# design.net
KiCad netlist of a schematic drawn in Altium Designer
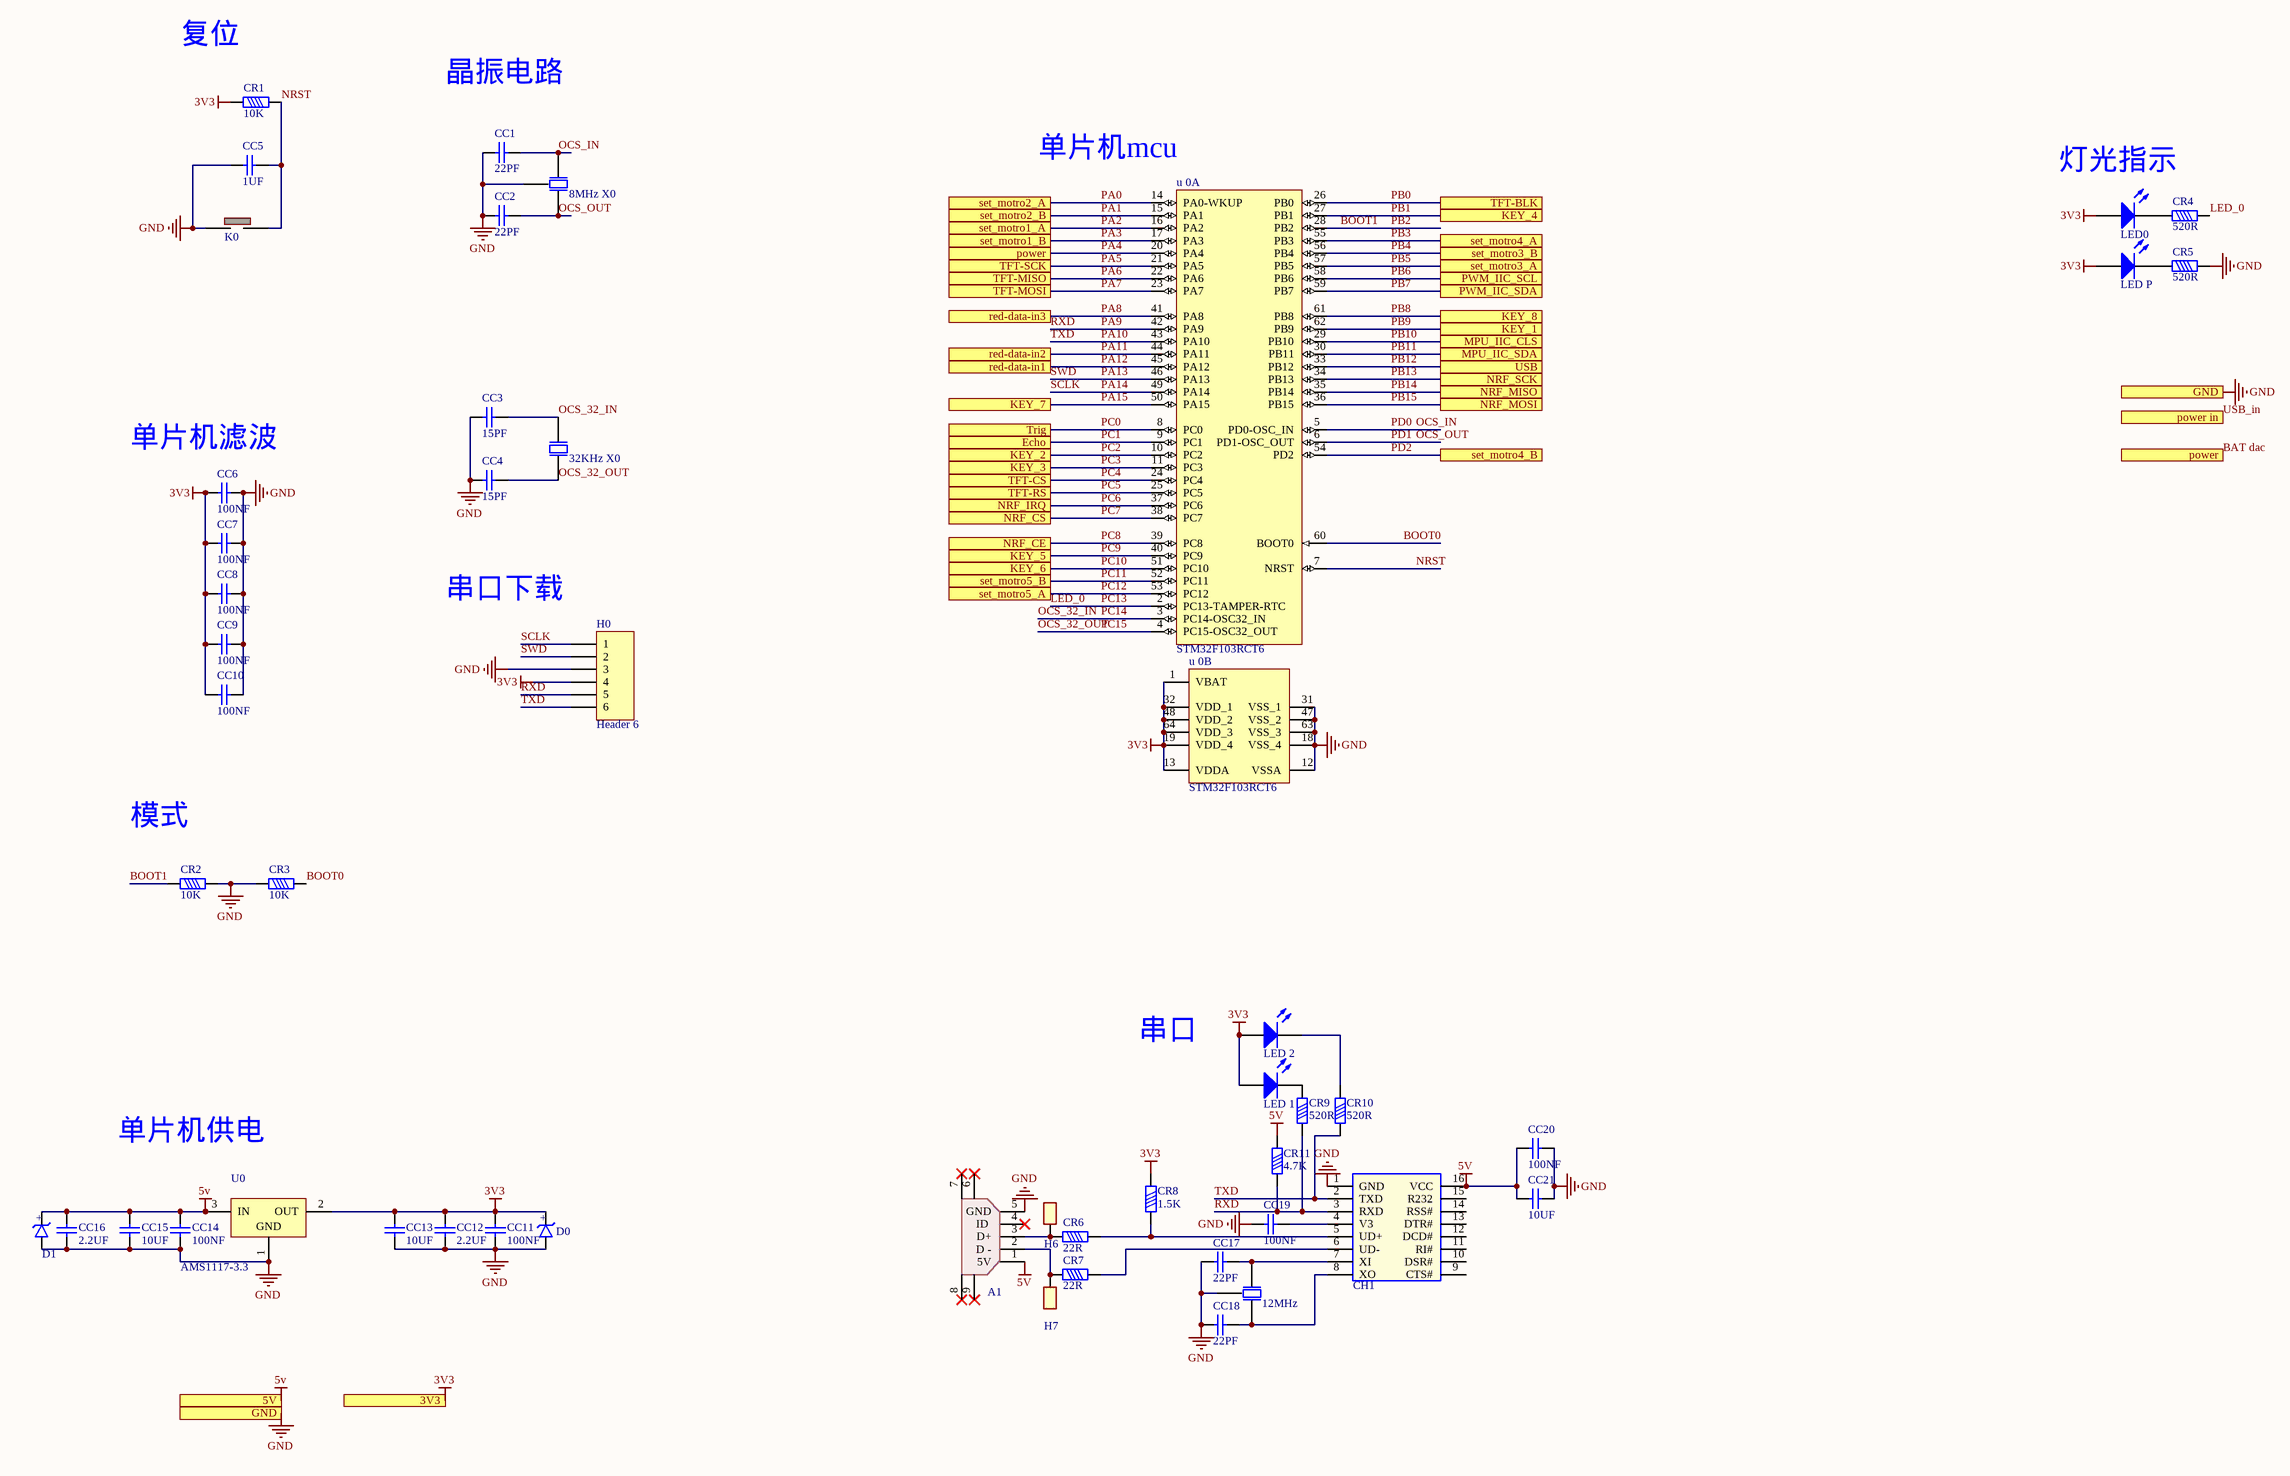
[diagram p0: 瓦力驱动主控原理图.SchDoc]

(export (version "E")
  (design (tool "Eeschema 10.0.6"))
  (components
    (comp (ref "8MHz X0")
      (value "XTAL 3225 8M")
      (footprint "T 3225")
      (libsource (lib "tianxiaohua_Schlib") (part "XTAL 3225 8M"))
    )
    (comp (ref "12MHz")
      (value "XTAL 3225 8M")
      (footprint "T 3225")
      (libsource (lib "tianxiaohua_Schlib") (part "XTAL 3225 8M"))
    )
    (comp (ref "32KHz X0")
      (value "XTAL 3215 32.768kKHz")
      (footprint "T 3215")
      (libsource (lib "tianxiaohua_Schlib") (part "XTAL 3215 32.768kKHz"))
    )
    (comp (ref "A1")
      (value "Micro USB")
      (footprint "Micro USB")
      (libsource (lib "tianxiaohua_Schlib") (part "Micro USB"))
    )
    (comp (ref "CC1")
      (value "22PF")
      (footprint "CC1608-0603")
      (description "Polarized Capacitor (Radial)")
      (fields (field (name "Comment") "Cap Chip 0603") (field (name "PUBLISHER") "Altium Limited"))
      (libsource (lib "EButterflyIntegratedLibrary") (part "Cap Chip 0603"))
    )
    (comp (ref "CC2")
      (value "22PF")
      (footprint "CC1608-0603")
      (description "Polarized Capacitor (Radial)")
      (fields (field (name "Comment") "Cap Chip 0603") (field (name "PUBLISHER") "Altium Limited"))
      (libsource (lib "EButterflyIntegratedLibrary") (part "Cap Chip 0603"))
    )
    (comp (ref "CC3")
      (value "15PF")
      (footprint "CC1608-0603")
      (description "Polarized Capacitor (Radial)")
      (fields (field (name "Comment") "Cap Chip 0603") (field (name "PUBLISHER") "Altium Limited"))
      (libsource (lib "EButterflyIntegratedLibrary") (part "Cap Chip 0603"))
    )
    (comp (ref "CC4")
      (value "15PF")
      (footprint "CC1608-0603")
      (description "Polarized Capacitor (Radial)")
      (fields (field (name "Comment") "Cap Chip 0603") (field (name "PUBLISHER") "Altium Limited"))
      (libsource (lib "EButterflyIntegratedLibrary") (part "Cap Chip 0603"))
    )
    (comp (ref "CC5")
      (value "1UF")
      (footprint "CC1608-0603")
      (description "Polarized Capacitor (Radial)")
      (fields (field (name "Comment") "Cap Chip 0603") (field (name "PUBLISHER") "Altium Limited"))
      (libsource (lib "EButterflyIntegratedLibrary") (part "Cap Chip 0603"))
    )
    (comp (ref "CC6")
      (value "100NF")
      (footprint "CC1608-0603")
      (description "Polarized Capacitor (Radial)")
      (fields (field (name "Comment") "Cap Chip 0603") (field (name "PUBLISHER") "Altium Limited"))
      (libsource (lib "EButterflyIntegratedLibrary") (part "Cap Chip 0603"))
    )
    (comp (ref "CC7")
      (value "100NF")
      (footprint "CC1608-0603")
      (description "Polarized Capacitor (Radial)")
      (fields (field (name "Comment") "Cap Chip 0603") (field (name "PUBLISHER") "Altium Limited"))
      (libsource (lib "EButterflyIntegratedLibrary") (part "Cap Chip 0603"))
    )
    (comp (ref "CC8")
      (value "100NF")
      (footprint "CC1608-0603")
      (description "Polarized Capacitor (Radial)")
      (fields (field (name "Comment") "Cap Chip 0603") (field (name "PUBLISHER") "Altium Limited"))
      (libsource (lib "EButterflyIntegratedLibrary") (part "Cap Chip 0603"))
    )
    (comp (ref "CC9")
      (value "100NF")
      (footprint "CC1608-0603")
      (description "Polarized Capacitor (Radial)")
      (fields (field (name "Comment") "Cap Chip 0603") (field (name "PUBLISHER") "Altium Limited"))
      (libsource (lib "EButterflyIntegratedLibrary") (part "Cap Chip 0603"))
    )
    (comp (ref "CC10")
      (value "100NF")
      (footprint "CC1608-0603")
      (description "Polarized Capacitor (Radial)")
      (fields (field (name "Comment") "Cap Chip 0603") (field (name "PUBLISHER") "Altium Limited"))
      (libsource (lib "EButterflyIntegratedLibrary") (part "Cap Chip 0603"))
    )
    (comp (ref "CC11")
      (value "100NF")
      (footprint "CC1608-0603")
      (description "Polarized Capacitor (Radial)")
      (fields (field (name "Comment") "Cap Chip 0603") (field (name "PUBLISHER") "Altium Limited"))
      (libsource (lib "EButterflyIntegratedLibrary") (part "Cap Chip 0603"))
    )
    (comp (ref "CC12")
      (value "2.2UF")
      (footprint "CC1608-0603")
      (description "Polarized Capacitor (Radial)")
      (fields (field (name "Comment") "Cap Chip 0603") (field (name "PUBLISHER") "Altium Limited"))
      (libsource (lib "EButterflyIntegratedLibrary") (part "Cap Chip 0603"))
    )
    (comp (ref "CC13")
      (value "10UF")
      (footprint "CC1608-0603")
      (description "Polarized Capacitor (Radial)")
      (fields (field (name "Comment") "Cap Chip 0603") (field (name "PUBLISHER") "Altium Limited"))
      (libsource (lib "EButterflyIntegratedLibrary") (part "Cap Chip 0603"))
    )
    (comp (ref "CC14")
      (value "100NF")
      (footprint "CC1608-0603")
      (description "Polarized Capacitor (Radial)")
      (fields (field (name "Comment") "Cap Chip 0603") (field (name "PUBLISHER") "Altium Limited"))
      (libsource (lib "EButterflyIntegratedLibrary") (part "Cap Chip 0603"))
    )
    (comp (ref "CC15")
      (value "10UF")
      (footprint "CC1608-0603")
      (description "Polarized Capacitor (Radial)")
      (fields (field (name "Comment") "Cap Chip 0603") (field (name "PUBLISHER") "Altium Limited"))
      (libsource (lib "EButterflyIntegratedLibrary") (part "Cap Chip 0603"))
    )
    (comp (ref "CC16")
      (value "2.2UF")
      (footprint "CC1608-0603")
      (description "Polarized Capacitor (Radial)")
      (fields (field (name "Comment") "Cap Chip 0603") (field (name "PUBLISHER") "Altium Limited"))
      (libsource (lib "EButterflyIntegratedLibrary") (part "Cap Chip 0603"))
    )
    (comp (ref "CC17")
      (value "22PF")
      (footprint "CC1608-0603")
      (description "Polarized Capacitor (Radial)")
      (fields (field (name "Comment") "Cap Chip 0603") (field (name "PUBLISHER") "Altium Limited"))
      (libsource (lib "EButterflyIntegratedLibrary") (part "Cap Chip 0603"))
    )
    (comp (ref "CC18")
      (value "22PF")
      (footprint "CC1608-0603")
      (description "Polarized Capacitor (Radial)")
      (fields (field (name "Comment") "Cap Chip 0603") (field (name "PUBLISHER") "Altium Limited"))
      (libsource (lib "EButterflyIntegratedLibrary") (part "Cap Chip 0603"))
    )
    (comp (ref "CC19")
      (value "100NF")
      (footprint "CC1608-0603")
      (description "Polarized Capacitor (Radial)")
      (fields (field (name "Comment") "Cap Chip 0603") (field (name "PUBLISHER") "Altium Limited"))
      (libsource (lib "EButterflyIntegratedLibrary") (part "Cap Chip 0603"))
    )
    (comp (ref "CC20")
      (value "100NF")
      (footprint "CC1608-0603")
      (description "Polarized Capacitor (Radial)")
      (fields (field (name "Comment") "Cap Chip 0603") (field (name "PUBLISHER") "Altium Limited"))
      (libsource (lib "EButterflyIntegratedLibrary") (part "Cap Chip 0603"))
    )
    (comp (ref "CC21")
      (value "10UF")
      (footprint "CC1608-0603")
      (description "Polarized Capacitor (Radial)")
      (fields (field (name "Comment") "Cap Chip 0603") (field (name "PUBLISHER") "Altium Limited"))
      (libsource (lib "EButterflyIntegratedLibrary") (part "Cap Chip 0603"))
    )
    (comp (ref "CH1")
      (value "CH340G")
      (footprint "SOP16")
      (description "串口转USB")
      (libsource (lib "tianxiaohua_Schlib") (part "CH340G"))
    )
    (comp (ref "CR1")
      (value "10K")
      (footprint "CR1608-0603")
      (description "Resistor")
      (fields (field (name "Comment") "Resistor Chip 0603") (field (name "PUBLISHER") "Altium Limited"))
      (libsource (lib "EButterflyIntegratedLibrary") (part "Resistor Chip 0603"))
    )
    (comp (ref "CR2")
      (value "10K")
      (footprint "CR1608-0603")
      (description "Resistor")
      (fields (field (name "Comment") "Resistor Chip 0603") (field (name "PUBLISHER") "Altium Limited"))
      (libsource (lib "EButterflyIntegratedLibrary") (part "Resistor Chip 0603"))
    )
    (comp (ref "CR3")
      (value "10K")
      (footprint "CR1608-0603")
      (description "Resistor")
      (fields (field (name "Comment") "Resistor Chip 0603") (field (name "PUBLISHER") "Altium Limited"))
      (libsource (lib "EButterflyIntegratedLibrary") (part "Resistor Chip 0603"))
    )
    (comp (ref "CR4")
      (value "520R")
      (footprint "CR1608-0603")
      (description "Resistor")
      (fields (field (name "Comment") "Resistor Chip 0603") (field (name "PUBLISHER") "Altium Limited"))
      (libsource (lib "EButterflyIntegratedLibrary") (part "Resistor Chip 0603"))
    )
    (comp (ref "CR5")
      (value "520R")
      (footprint "CR1608-0603")
      (description "Resistor")
      (fields (field (name "Comment") "Resistor Chip 0603") (field (name "PUBLISHER") "Altium Limited"))
      (libsource (lib "EButterflyIntegratedLibrary") (part "Resistor Chip 0603"))
    )
    (comp (ref "CR6")
      (value "22R")
      (footprint "CR1608-0603")
      (description "Resistor")
      (fields (field (name "Comment") "Resistor Chip 0603") (field (name "PUBLISHER") "Altium Limited"))
      (libsource (lib "EButterflyIntegratedLibrary") (part "Resistor Chip 0603"))
    )
    (comp (ref "CR7")
      (value "22R")
      (footprint "CR1608-0603")
      (description "Resistor")
      (fields (field (name "Comment") "Resistor Chip 0603") (field (name "PUBLISHER") "Altium Limited"))
      (libsource (lib "EButterflyIntegratedLibrary") (part "Resistor Chip 0603"))
    )
    (comp (ref "CR8")
      (value "1.5K")
      (footprint "CR1608-0603")
      (description "Resistor")
      (fields (field (name "Comment") "Resistor Chip 0603") (field (name "PUBLISHER") "Altium Limited"))
      (libsource (lib "") (part "Resistor Chip 0603_1"))
    )
    (comp (ref "CR9")
      (value "520R")
      (footprint "CR1608-0603")
      (description "Resistor")
      (fields (field (name "Comment") "Resistor Chip 0603") (field (name "PUBLISHER") "Altium Limited"))
      (libsource (lib "") (part "Resistor Chip 0603_1"))
    )
    (comp (ref "CR10")
      (value "520R")
      (footprint "CR1608-0603")
      (description "Resistor")
      (fields (field (name "Comment") "Resistor Chip 0603") (field (name "PUBLISHER") "Altium Limited"))
      (libsource (lib "") (part "Resistor Chip 0603_1"))
    )
    (comp (ref "CR11")
      (value "4.7K")
      (footprint "CR1608-0603")
      (description "Resistor")
      (fields (field (name "Comment") "Resistor Chip 0603") (field (name "PUBLISHER") "Altium Limited"))
      (libsource (lib "") (part "Resistor Chip 0603_1"))
    )
    (comp (ref "D0")
      (value "SMBJ3.3A")
      (footprint "DO214AA(SMB)")
      (description "3.3V稳压管，缓解瞬间电压冲击")
      (libsource (lib "tianxiaohua_Schlib") (part "SMBJ3.3A"))
    )
    (comp (ref "D1")
      (value "SMBJ3.3A")
      (footprint "DO214AA(SMB)")
      (description "3.3V稳压管，缓解瞬间电压冲击")
      (libsource (lib "tianxiaohua_Schlib") (part "SMBJ3.3A"))
    )
    (comp (ref "H0")
      (value "Header 6")
      (footprint "HDR1X6")
      (description "Header, 6-Pin")
      (fields (field (name "PUBLISHER") "Altium Limited"))
      (libsource (lib "EButterflyIntegratedLibrary") (part "Header 6"))
    )
    (comp (ref "H6")
      (value "H0")
      (footprint "header 1")
      (libsource (lib "tianxiaohua_Schlib") (part "header 1"))
    )
    (comp (ref "H7") (value "H0") (footprint "header 1") (libsource (lib "") (part "header 1_1")))
    (comp (ref "K0")
      (value "KEY 3*4")
      (footprint "KEY 3*4")
      (libsource (lib "tianxiaohua_Schlib") (part "KEY 3*4"))
    )
    (comp (ref "LED 1")
      (value "LED Chip")
      (footprint "CLED1608-0603")
      (description "Typical Chip LED")
      (fields (field (name "PUBLISHER") "Altium Limited"))
      (libsource (lib "EButterflyIntegratedLibrary") (part "LED Chip"))
    )
    (comp (ref "LED 2")
      (value "LED Chip")
      (footprint "CLED1608-0603")
      (description "Typical Chip LED")
      (fields (field (name "PUBLISHER") "Altium Limited"))
      (libsource (lib "EButterflyIntegratedLibrary") (part "LED Chip"))
    )
    (comp (ref "LED P")
      (value "LED Chip")
      (footprint "CLED1608-0603")
      (description "Typical Chip LED")
      (fields (field (name "PUBLISHER") "Altium Limited"))
      (libsource (lib "EButterflyIntegratedLibrary") (part "LED Chip"))
    )
    (comp (ref "LED0")
      (value "LED Chip")
      (footprint "CLED1608-0603")
      (description "Typical Chip LED")
      (fields (field (name "PUBLISHER") "Altium Limited"))
      (libsource (lib "EButterflyIntegratedLibrary") (part "LED Chip"))
    )
    (comp (ref "u 0")
      (value "STM32F103RCT6")
      (footprint "STM-LQFP64_N")
      (libsource (lib "STMicroelectronics STM32 F1") (part "STM32F103RCT6"))
    )
    (comp (ref "U0")
      (value "AMS1117-3.3")
      (footprint "SOT-223")
      (description "POSITIVE OUTPUT VOLTAGE")
      (libsource (lib "EButterflyIntegratedLibrary") (part "AMS1117"))
    )
  )
  (nets
    (net (code "1") (name "/BAT dac") (class "Default")
      (node (ref "u 0") (pin "20") (pinfunction "PA4_20") (pintype "bidirectional"))
    )
    (net (code "2") (name "/BOOT0") (class "Default")
      (node (ref "CR3") (pin "2") (pinfunction "2_2") (pintype "passive"))
      (node (ref "u 0") (pin "60") (pinfunction "BOOT0_60") (pintype "input"))
    )
    (net (code "3") (name "/BOOT1") (class "Default")
      (node (ref "CR2") (pin "1") (pinfunction "1_1") (pintype "passive"))
      (node (ref "u 0") (pin "28") (pinfunction "PB2_28") (pintype "bidirectional"))
    )
    (net (code "4") (name "/LED_0") (class "Default")
      (node (ref "CR4") (pin "2") (pinfunction "2_2") (pintype "passive"))
      (node (ref "u 0") (pin "2") (pinfunction "PC13-TAMPER-RTC_2") (pintype "bidirectional"))
    )
    (net (code "5") (name "/NRST") (class "Default")
      (node (ref "CC5") (pin "2") (pinfunction "2_2") (pintype "passive"))
      (node (ref "CR1") (pin "2") (pinfunction "2_2") (pintype "passive"))
      (node (ref "K0") (pin "2") (pinfunction "2_2") (pintype "passive"))
      (node (ref "u 0") (pin "7") (pinfunction "NRST_7") (pintype "bidirectional"))
    )
    (net (code "6") (name "/OCS_32_IN") (class "Default")
      (node (ref "32KHz X0") (pin "2") (pinfunction "OSC2_2") (pintype "passive"))
      (node (ref "CC3") (pin "2") (pinfunction "2_2") (pintype "passive"))
      (node (ref "u 0") (pin "3") (pinfunction "PC14-OSC32_IN_3") (pintype "bidirectional"))
    )
    (net (code "7") (name "/OCS_32_OUT") (class "Default")
      (node (ref "32KHz X0") (pin "1") (pinfunction "OSC1_1") (pintype "passive"))
      (node (ref "CC4") (pin "2") (pinfunction "2_2") (pintype "passive"))
      (node (ref "u 0") (pin "4") (pinfunction "PC15-OSC32_OUT_4") (pintype "bidirectional"))
    )
    (net (code "8") (name "/OCS_IN") (class "Default")
      (node (ref "8MHz X0") (pin "1") (pinfunction "OSC1_1") (pintype "passive"))
      (node (ref "CC1") (pin "2") (pinfunction "2_2") (pintype "passive"))
      (node (ref "u 0") (pin "5") (pinfunction "PD0-OSC_IN_5") (pintype "bidirectional"))
    )
    (net (code "9") (name "/OCS_OUT") (class "Default")
      (node (ref "8MHz X0") (pin "2") (pinfunction "OSC2_2") (pintype "passive"))
      (node (ref "CC2") (pin "2") (pinfunction "2_2") (pintype "passive"))
      (node (ref "u 0") (pin "6") (pinfunction "PD1-OSC_OUT_6") (pintype "bidirectional"))
    )
    (net (code "10") (name "/PA0") (class "Default")
      (node (ref "u 0") (pin "14") (pinfunction "PA0-WKUP_14") (pintype "bidirectional"))
    )
    (net (code "11") (name "/PA1") (class "Default")
      (node (ref "u 0") (pin "15") (pinfunction "PA1_15") (pintype "bidirectional"))
    )
    (net (code "12") (name "/PA2") (class "Default")
      (node (ref "u 0") (pin "16") (pinfunction "PA2_16") (pintype "bidirectional"))
    )
    (net (code "13") (name "/PA3") (class "Default")
      (node (ref "u 0") (pin "17") (pinfunction "PA3_17") (pintype "bidirectional"))
    )
    (net (code "14") (name "/PA6") (class "Default")
      (node (ref "u 0") (pin "22") (pinfunction "PA6_22") (pintype "bidirectional"))
    )
    (net (code "15") (name "/PA7") (class "Default")
      (node (ref "u 0") (pin "23") (pinfunction "PA7_23") (pintype "bidirectional"))
    )
    (net (code "16") (name "/PA8") (class "Default")
      (node (ref "u 0") (pin "41") (pinfunction "PA8_41") (pintype "bidirectional"))
    )
    (net (code "17") (name "/PA9") (class "Default")
      (node (ref "CH1") (pin "3") (pinfunction "RXD_3") (pintype "passive"))
      (node (ref "CR11") (pin "1") (pinfunction "1_1") (pintype "passive"))
      (node (ref "CR9") (pin "1") (pinfunction "1_1") (pintype "passive"))
      (node (ref "H0") (pin "5") (pinfunction "5_5") (pintype "passive"))
      (node (ref "u 0") (pin "42") (pinfunction "PA9_42") (pintype "bidirectional"))
    )
    (net (code "18") (name "/PA10") (class "Default")
      (node (ref "CH1") (pin "2") (pinfunction "TXD_2") (pintype "passive"))
      (node (ref "CR10") (pin "1") (pinfunction "1_1") (pintype "passive"))
      (node (ref "H0") (pin "6") (pinfunction "6_6") (pintype "passive"))
      (node (ref "u 0") (pin "43") (pinfunction "PA10_43") (pintype "bidirectional"))
    )
    (net (code "19") (name "/PA11") (class "Default")
      (node (ref "u 0") (pin "44") (pinfunction "PA11_44") (pintype "bidirectional"))
    )
    (net (code "20") (name "/PA12") (class "Default")
      (node (ref "u 0") (pin "45") (pinfunction "PA12_45") (pintype "bidirectional"))
    )
    (net (code "21") (name "/PA13") (class "Default")
      (node (ref "H0") (pin "2") (pinfunction "2_2") (pintype "passive"))
      (node (ref "u 0") (pin "46") (pinfunction "PA13_46") (pintype "bidirectional"))
    )
    (net (code "22") (name "/PA14") (class "Default")
      (node (ref "H0") (pin "1") (pinfunction "1_1") (pintype "passive"))
      (node (ref "u 0") (pin "49") (pinfunction "PA14_49") (pintype "bidirectional"))
    )
    (net (code "23") (name "/PA15") (class "Default")
      (node (ref "u 0") (pin "50") (pinfunction "PA15_50") (pintype "bidirectional"))
    )
    (net (code "24") (name "/PA~{5}") (class "Default")
      (node (ref "u 0") (pin "21") (pinfunction "PA5_21") (pintype "bidirectional"))
    )
    (net (code "25") (name "/PB0") (class "Default")
      (node (ref "u 0") (pin "26") (pinfunction "PB0_26") (pintype "bidirectional"))
    )
    (net (code "26") (name "/PB1") (class "Default")
      (node (ref "u 0") (pin "27") (pinfunction "PB1_27") (pintype "bidirectional"))
    )
    (net (code "27") (name "/PB3") (class "Default")
      (node (ref "u 0") (pin "55") (pinfunction "PB3_55") (pintype "bidirectional"))
    )
    (net (code "28") (name "/PB4") (class "Default")
      (node (ref "u 0") (pin "56") (pinfunction "PB4_56") (pintype "bidirectional"))
    )
    (net (code "29") (name "/PB5") (class "Default")
      (node (ref "u 0") (pin "57") (pinfunction "PB5_57") (pintype "bidirectional"))
    )
    (net (code "30") (name "/PB6") (class "Default")
      (node (ref "u 0") (pin "58") (pinfunction "PB6_58") (pintype "bidirectional"))
    )
    (net (code "31") (name "/PB7") (class "Default")
      (node (ref "u 0") (pin "59") (pinfunction "PB7_59") (pintype "bidirectional"))
    )
    (net (code "32") (name "/PB8") (class "Default")
      (node (ref "u 0") (pin "61") (pinfunction "PB8_61") (pintype "bidirectional"))
    )
    (net (code "33") (name "/PB9") (class "Default")
      (node (ref "u 0") (pin "62") (pinfunction "PB9_62") (pintype "bidirectional"))
    )
    (net (code "34") (name "/PB10") (class "Default")
      (node (ref "u 0") (pin "29") (pinfunction "PB10_29") (pintype "bidirectional"))
    )
    (net (code "35") (name "/PB11") (class "Default")
      (node (ref "u 0") (pin "30") (pinfunction "PB11_30") (pintype "bidirectional"))
    )
    (net (code "36") (name "/PB12") (class "Default")
      (node (ref "u 0") (pin "33") (pinfunction "PB12_33") (pintype "bidirectional"))
    )
    (net (code "37") (name "/PB13") (class "Default")
      (node (ref "u 0") (pin "34") (pinfunction "PB13_34") (pintype "bidirectional"))
    )
    (net (code "38") (name "/PB14") (class "Default")
      (node (ref "u 0") (pin "35") (pinfunction "PB14_35") (pintype "bidirectional"))
    )
    (net (code "39") (name "/PB15") (class "Default")
      (node (ref "u 0") (pin "36") (pinfunction "PB15_36") (pintype "bidirectional"))
    )
    (net (code "40") (name "/PC0") (class "Default")
      (node (ref "u 0") (pin "8") (pinfunction "PC0_8") (pintype "bidirectional"))
    )
    (net (code "41") (name "/PC1") (class "Default")
      (node (ref "u 0") (pin "9") (pinfunction "PC1_9") (pintype "bidirectional"))
    )
    (net (code "42") (name "/PC2") (class "Default")
      (node (ref "u 0") (pin "10") (pinfunction "PC2_10") (pintype "bidirectional"))
    )
    (net (code "43") (name "/PC3") (class "Default")
      (node (ref "u 0") (pin "11") (pinfunction "PC3_11") (pintype "bidirectional"))
    )
    (net (code "44") (name "/PC4") (class "Default")
      (node (ref "u 0") (pin "24") (pinfunction "PC4_24") (pintype "bidirectional"))
    )
    (net (code "45") (name "/PC5") (class "Default")
      (node (ref "u 0") (pin "25") (pinfunction "PC5_25") (pintype "bidirectional"))
    )
    (net (code "46") (name "/PC6") (class "Default")
      (node (ref "u 0") (pin "37") (pinfunction "PC6_37") (pintype "bidirectional"))
    )
    (net (code "47") (name "/PC7") (class "Default")
      (node (ref "u 0") (pin "38") (pinfunction "PC7_38") (pintype "bidirectional"))
    )
    (net (code "48") (name "/PC8") (class "Default")
      (node (ref "u 0") (pin "39") (pinfunction "PC8_39") (pintype "bidirectional"))
    )
    (net (code "49") (name "/PC9") (class "Default")
      (node (ref "u 0") (pin "40") (pinfunction "PC9_40") (pintype "bidirectional"))
    )
    (net (code "50") (name "/PC10") (class "Default")
      (node (ref "u 0") (pin "51") (pinfunction "PC10_51") (pintype "bidirectional"))
    )
    (net (code "51") (name "/PC11") (class "Default")
      (node (ref "u 0") (pin "52") (pinfunction "PC11_52") (pintype "bidirectional"))
    )
    (net (code "52") (name "/PC12") (class "Default")
      (node (ref "u 0") (pin "53") (pinfunction "PC12_53") (pintype "bidirectional"))
    )
    (net (code "53") (name "/PD2") (class "Default")
      (node (ref "u 0") (pin "54") (pinfunction "PD2_54") (pintype "bidirectional"))
    )
    (net (code "55") (name "3V3") (class "Default")
      (node (ref "CC10") (pin "1") (pinfunction "1_1") (pintype "passive"))
      (node (ref "CC11") (pin "2") (pinfunction "2_2") (pintype "passive"))
      (node (ref "CC12") (pin "2") (pinfunction "2_2") (pintype "passive"))
      (node (ref "CC13") (pin "2") (pinfunction "2_2") (pintype "passive"))
      (node (ref "CC6") (pin "1") (pinfunction "1_1") (pintype "passive"))
      (node (ref "CC7") (pin "1") (pinfunction "1_1") (pintype "passive"))
      (node (ref "CC8") (pin "1") (pinfunction "1_1") (pintype "passive"))
      (node (ref "CC9") (pin "1") (pinfunction "1_1") (pintype "passive"))
      (node (ref "CR1") (pin "1") (pinfunction "1_1") (pintype "passive"))
      (node (ref "CR8") (pin "2") (pinfunction "2_2") (pintype "passive"))
      (node (ref "D0") (pin "1") (pinfunction "1_1") (pintype "passive"))
      (node (ref "H0") (pin "4") (pinfunction "4_4") (pintype "passive"))
      (node (ref "LED 1") (pin "1") (pinfunction "A_1") (pintype "passive"))
      (node (ref "LED 2") (pin "1") (pinfunction "A_1") (pintype "passive"))
      (node (ref "LED P") (pin "1") (pinfunction "A_1") (pintype "passive"))
      (node (ref "LED0") (pin "1") (pinfunction "A_1") (pintype "passive"))
      (node (ref "U0") (pin "2") (pinfunction "OUT_2") (pintype "power_in"))
      (node (ref "u 0") (pin "1") (pinfunction "VBAT_1") (pintype "power_in"))
      (node (ref "u 0") (pin "13") (pinfunction "VDDA_13") (pintype "power_in"))
      (node (ref "u 0") (pin "19") (pinfunction "VDD_4_19") (pintype "power_in"))
      (node (ref "u 0") (pin "32") (pinfunction "VDD_1_32") (pintype "power_in"))
      (node (ref "u 0") (pin "48") (pinfunction "VDD_2_48") (pintype "power_in"))
      (node (ref "u 0") (pin "64") (pinfunction "VDD_3_64") (pintype "power_in"))
    )
    (net (code "56") (name "5V") (class "Default")
      (node (ref "A1") (pin "1") (pinfunction "5V_1") (pintype "passive"))
      (node (ref "CC14") (pin "2") (pinfunction "2_2") (pintype "passive"))
      (node (ref "CC15") (pin "2") (pinfunction "2_2") (pintype "passive"))
      (node (ref "CC16") (pin "2") (pinfunction "2_2") (pintype "passive"))
      (node (ref "CC20") (pin "1") (pinfunction "1_1") (pintype "passive"))
      (node (ref "CC21") (pin "1") (pinfunction "1_1") (pintype "passive"))
      (node (ref "CH1") (pin "16") (pinfunction "VCC_16") (pintype "passive"))
      (node (ref "CR11") (pin "2") (pinfunction "2_2") (pintype "passive"))
      (node (ref "D1") (pin "1") (pinfunction "1_1") (pintype "passive"))
      (node (ref "U0") (pin "3") (pinfunction "IN_3") (pintype "power_in"))
    )
    (net (code "57") (name "GND") (class "Default")
      (node (ref "12MHz") (pin "3") (pinfunction "GND_3") (pintype "passive"))
      (node (ref "8MHz X0") (pin "3") (pinfunction "GND_3") (pintype "passive"))
      (node (ref "A1") (pin "5") (pinfunction "GND_5") (pintype "passive"))
      (node (ref "CC1") (pin "1") (pinfunction "1_1") (pintype "passive"))
      (node (ref "CC10") (pin "2") (pinfunction "2_2") (pintype "passive"))
      (node (ref "CC11") (pin "1") (pinfunction "1_1") (pintype "passive"))
      (node (ref "CC12") (pin "1") (pinfunction "1_1") (pintype "passive"))
      (node (ref "CC13") (pin "1") (pinfunction "1_1") (pintype "passive"))
      (node (ref "CC14") (pin "1") (pinfunction "1_1") (pintype "passive"))
      (node (ref "CC15") (pin "1") (pinfunction "1_1") (pintype "passive"))
      (node (ref "CC16") (pin "1") (pinfunction "1_1") (pintype "passive"))
      (node (ref "CC17") (pin "1") (pinfunction "1_1") (pintype "passive"))
      (node (ref "CC18") (pin "1") (pinfunction "1_1") (pintype "passive"))
      (node (ref "CC19") (pin "1") (pinfunction "1_1") (pintype "passive"))
      (node (ref "CC2") (pin "1") (pinfunction "1_1") (pintype "passive"))
      (node (ref "CC20") (pin "2") (pinfunction "2_2") (pintype "passive"))
      (node (ref "CC21") (pin "2") (pinfunction "2_2") (pintype "passive"))
      (node (ref "CC3") (pin "1") (pinfunction "1_1") (pintype "passive"))
      (node (ref "CC4") (pin "1") (pinfunction "1_1") (pintype "passive"))
      (node (ref "CC5") (pin "1") (pinfunction "1_1") (pintype "passive"))
      (node (ref "CC6") (pin "2") (pinfunction "2_2") (pintype "passive"))
      (node (ref "CC7") (pin "2") (pinfunction "2_2") (pintype "passive"))
      (node (ref "CC8") (pin "2") (pinfunction "2_2") (pintype "passive"))
      (node (ref "CC9") (pin "2") (pinfunction "2_2") (pintype "passive"))
      (node (ref "CH1") (pin "1") (pinfunction "GND_1") (pintype "passive"))
      (node (ref "CR2") (pin "2") (pinfunction "2_2") (pintype "passive"))
      (node (ref "CR3") (pin "1") (pinfunction "1_1") (pintype "passive"))
      (node (ref "CR5") (pin "2") (pinfunction "2_2") (pintype "passive"))
      (node (ref "D0") (pin "2") (pinfunction "2_2") (pintype "passive"))
      (node (ref "D1") (pin "2") (pinfunction "2_2") (pintype "passive"))
      (node (ref "H0") (pin "3") (pinfunction "3_3") (pintype "passive"))
      (node (ref "K0") (pin "1") (pinfunction "1_1") (pintype "passive"))
      (node (ref "U0") (pin "1") (pinfunction "GND_1") (pintype "power_in"))
      (node (ref "u 0") (pin "12") (pinfunction "VSSA_12") (pintype "power_in"))
      (node (ref "u 0") (pin "18") (pinfunction "VSS_4_18") (pintype "power_in"))
      (node (ref "u 0") (pin "31") (pinfunction "VSS_1_31") (pintype "power_in"))
      (node (ref "u 0") (pin "47") (pinfunction "VSS_2_47") (pintype "power_in"))
      (node (ref "u 0") (pin "63") (pinfunction "VSS_3_63") (pintype "power_in"))
    )
    (net (code "58") (name "Net-(12MHz-OSC1)") (class "Default")
      (node (ref "12MHz") (pin "1") (pinfunction "OSC1_1") (pintype "passive"))
      (node (ref "CC17") (pin "2") (pinfunction "2_2") (pintype "passive"))
      (node (ref "CH1") (pin "7") (pinfunction "XI_7") (pintype "passive"))
    )
    (net (code "59") (name "Net-(12MHz-OSC2)") (class "Default")
      (node (ref "12MHz") (pin "2") (pinfunction "OSC2_2") (pintype "passive"))
      (node (ref "CC18") (pin "2") (pinfunction "2_2") (pintype "passive"))
      (node (ref "CH1") (pin "8") (pinfunction "XO_8") (pintype "passive"))
    )
    (net (code "60") (name "Net-(A1-D+)") (class "Default")
      (node (ref "A1") (pin "3") (pinfunction "D+_3") (pintype "passive"))
      (node (ref "CR6") (pin "1") (pinfunction "1_1") (pintype "passive"))
      (node (ref "H6") (pin "1") (pinfunction "1_1") (pintype "passive"))
    )
    (net (code "61") (name "Net-(A1-D_-)") (class "Default")
      (node (ref "A1") (pin "2") (pinfunction "D_-_2") (pintype "passive"))
      (node (ref "CR7") (pin "1") (pinfunction "1_1") (pintype "passive"))
      (node (ref "H7") (pin "1") (pinfunction "1_1") (pintype "passive"))
    )
    (net (code "62") (name "Net-(CH1-UD+)") (class "Default")
      (node (ref "CH1") (pin "5") (pinfunction "UD+_5") (pintype "passive"))
      (node (ref "CR6") (pin "2") (pinfunction "2_2") (pintype "passive"))
      (node (ref "CR8") (pin "1") (pinfunction "1_1") (pintype "passive"))
    )
    (net (code "63") (name "Net-(CH1-UD-)") (class "Default")
      (node (ref "CH1") (pin "6") (pinfunction "UD-_6") (pintype "passive"))
      (node (ref "CR7") (pin "2") (pinfunction "2_2") (pintype "passive"))
    )
    (net (code "64") (name "Net-(CH1-V3)") (class "Default")
      (node (ref "CC19") (pin "2") (pinfunction "2_2") (pintype "passive"))
      (node (ref "CH1") (pin "4") (pinfunction "V3_4") (pintype "passive"))
    )
    (net (code "65") (name "Net-(LED 1-K)") (class "Default")
      (node (ref "CR9") (pin "2") (pinfunction "2_2") (pintype "passive"))
      (node (ref "LED 1") (pin "2") (pinfunction "K_2") (pintype "passive"))
    )
    (net (code "66") (name "Net-(LED 2-K)") (class "Default")
      (node (ref "CR10") (pin "2") (pinfunction "2_2") (pintype "passive"))
      (node (ref "LED 2") (pin "2") (pinfunction "K_2") (pintype "passive"))
    )
    (net (code "67") (name "Net-(LED P-K)") (class "Default")
      (node (ref "CR5") (pin "1") (pinfunction "1_1") (pintype "passive"))
      (node (ref "LED P") (pin "2") (pinfunction "K_2") (pintype "passive"))
    )
    (net (code "68") (name "Net-(LED0-K)") (class "Default")
      (node (ref "CR4") (pin "1") (pinfunction "1_1") (pintype "passive"))
      (node (ref "LED0") (pin "2") (pinfunction "K_2") (pintype "passive"))
    )
    (net (code "69") (name "unconnected-(A1-ID-Pad4)") (class "Default")
      (node (ref "A1") (pin "4") (pinfunction "ID_4") (pintype "passive+no_connect"))
    )
    (net (code "70") (name "unconnected-(A1-Pad6)") (class "Default")
      (node (ref "A1") (pin "6") (pinfunction "6_6") (pintype "passive+no_connect"))
    )
    (net (code "71") (name "unconnected-(A1-Pad7)") (class "Default")
      (node (ref "A1") (pin "7") (pinfunction "7_7") (pintype "passive+no_connect"))
    )
    (net (code "72") (name "unconnected-(A1-Pad8)") (class "Default")
      (node (ref "A1") (pin "8") (pinfunction "8_8") (pintype "passive+no_connect"))
    )
    (net (code "73") (name "unconnected-(A1-Pad9)") (class "Default")
      (node (ref "A1") (pin "9") (pinfunction "9_9") (pintype "passive+no_connect"))
    )
    (net (code "74") (name "unconnected-(CH1-CTS#-Pad9)") (class "Default")
      (node (ref "CH1") (pin "9") (pinfunction "CTS#_9") (pintype "passive"))
    )
    (net (code "75") (name "unconnected-(CH1-DCD#-Pad12)") (class "Default")
      (node (ref "CH1") (pin "12") (pinfunction "DCD#_12") (pintype "passive"))
    )
    (net (code "76") (name "unconnected-(CH1-DSR#-Pad10)") (class "Default")
      (node (ref "CH1") (pin "10") (pinfunction "DSR#_10") (pintype "passive"))
    )
    (net (code "77") (name "unconnected-(CH1-DTR#-Pad13)") (class "Default")
      (node (ref "CH1") (pin "13") (pinfunction "DTR#_13") (pintype "passive"))
    )
    (net (code "78") (name "unconnected-(CH1-R232-Pad15)") (class "Default")
      (node (ref "CH1") (pin "15") (pinfunction "R232_15") (pintype "passive"))
    )
    (net (code "79") (name "unconnected-(CH1-RI#-Pad11)") (class "Default")
      (node (ref "CH1") (pin "11") (pinfunction "RI#_11") (pintype "passive"))
    )
    (net (code "80") (name "unconnected-(CH1-RSS#-Pad14)") (class "Default")
      (node (ref "CH1") (pin "14") (pinfunction "RSS#_14") (pintype "passive"))
    )
  )
)
